# G888-mk2.net
KiCad netlist of a schematic drawn in EAGLE
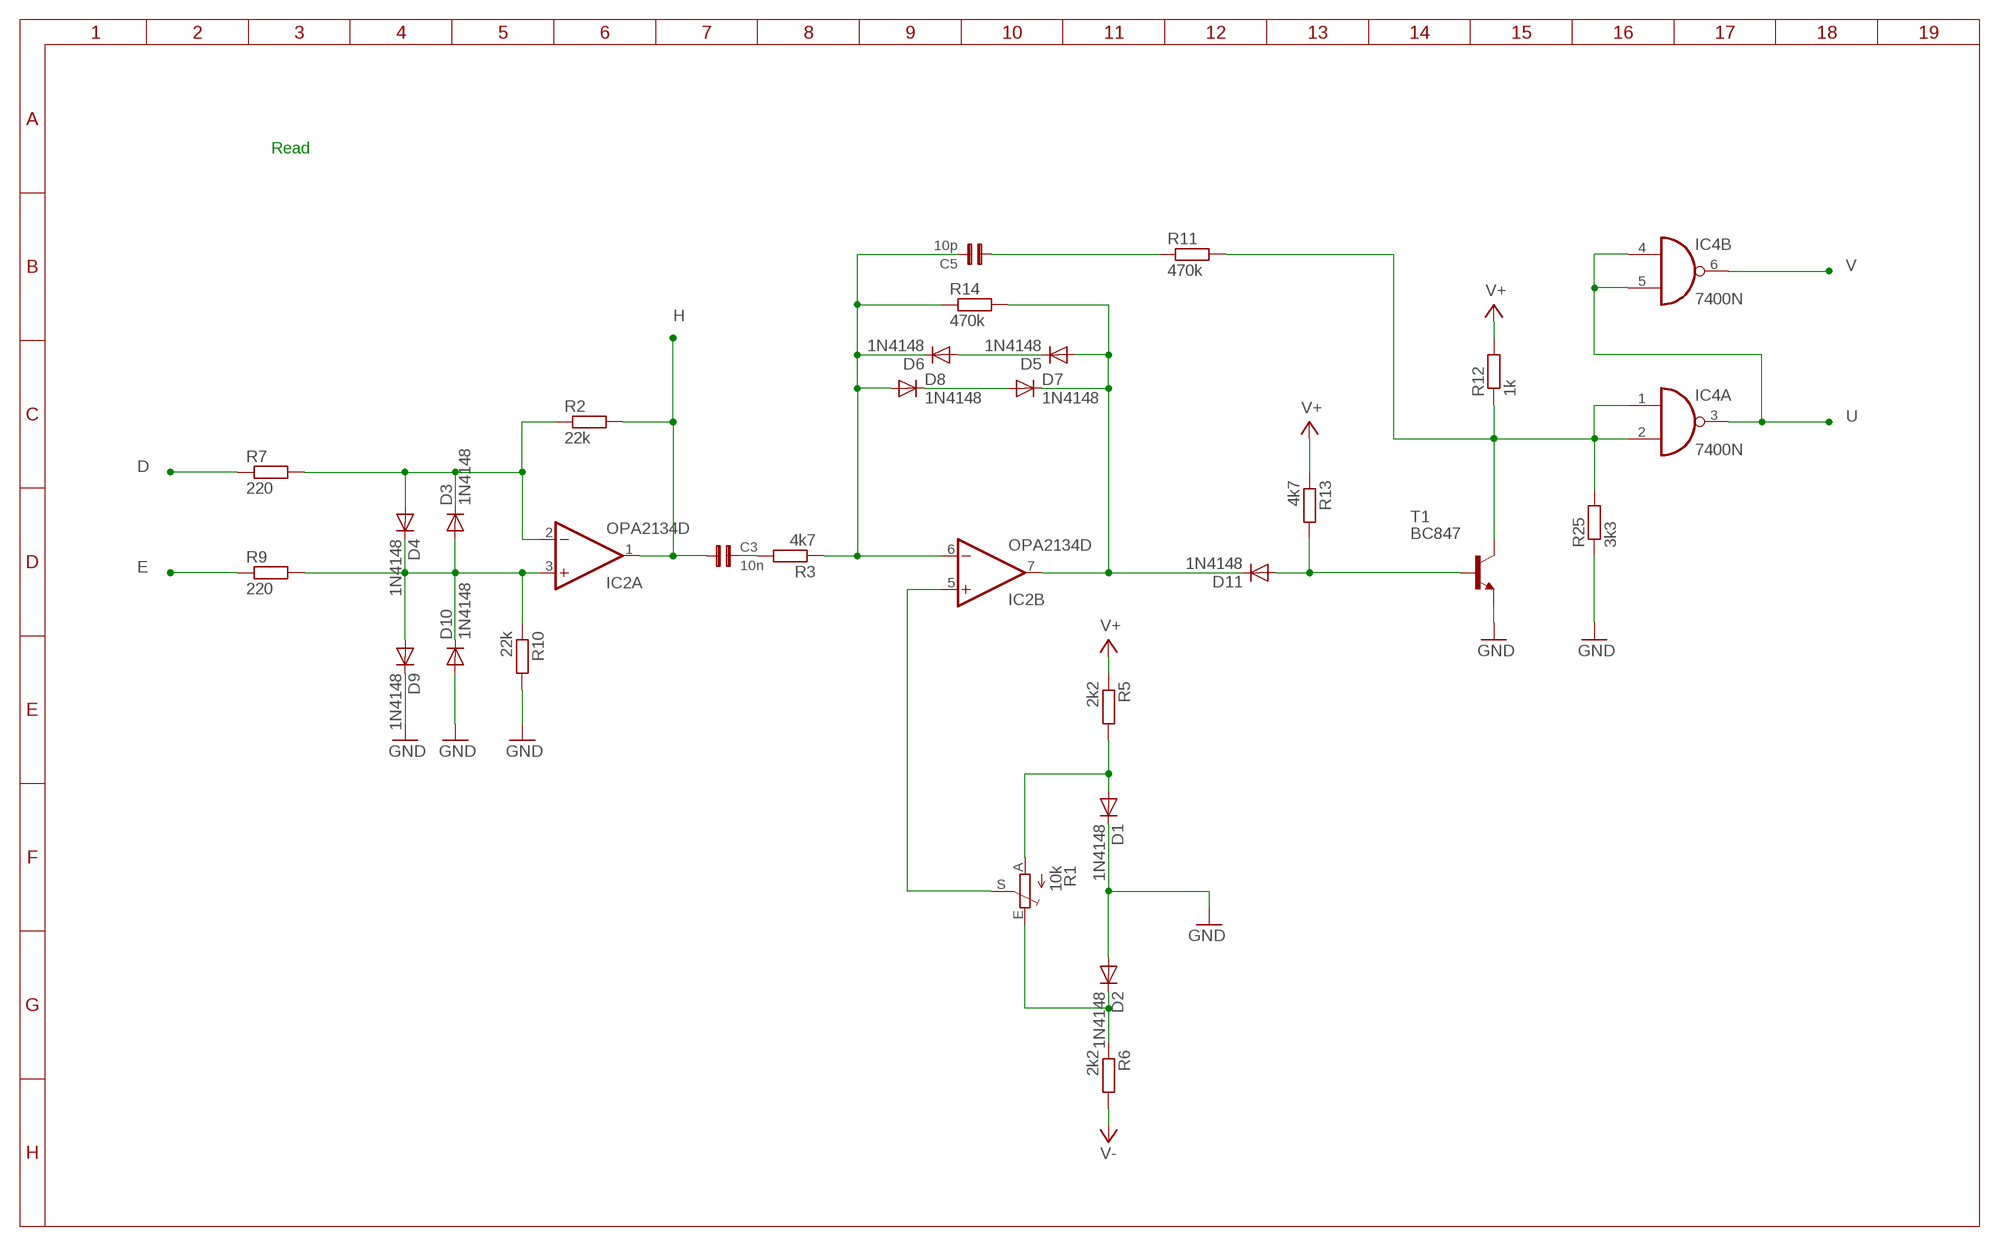
[diagram p0: schematic, sheet 1]
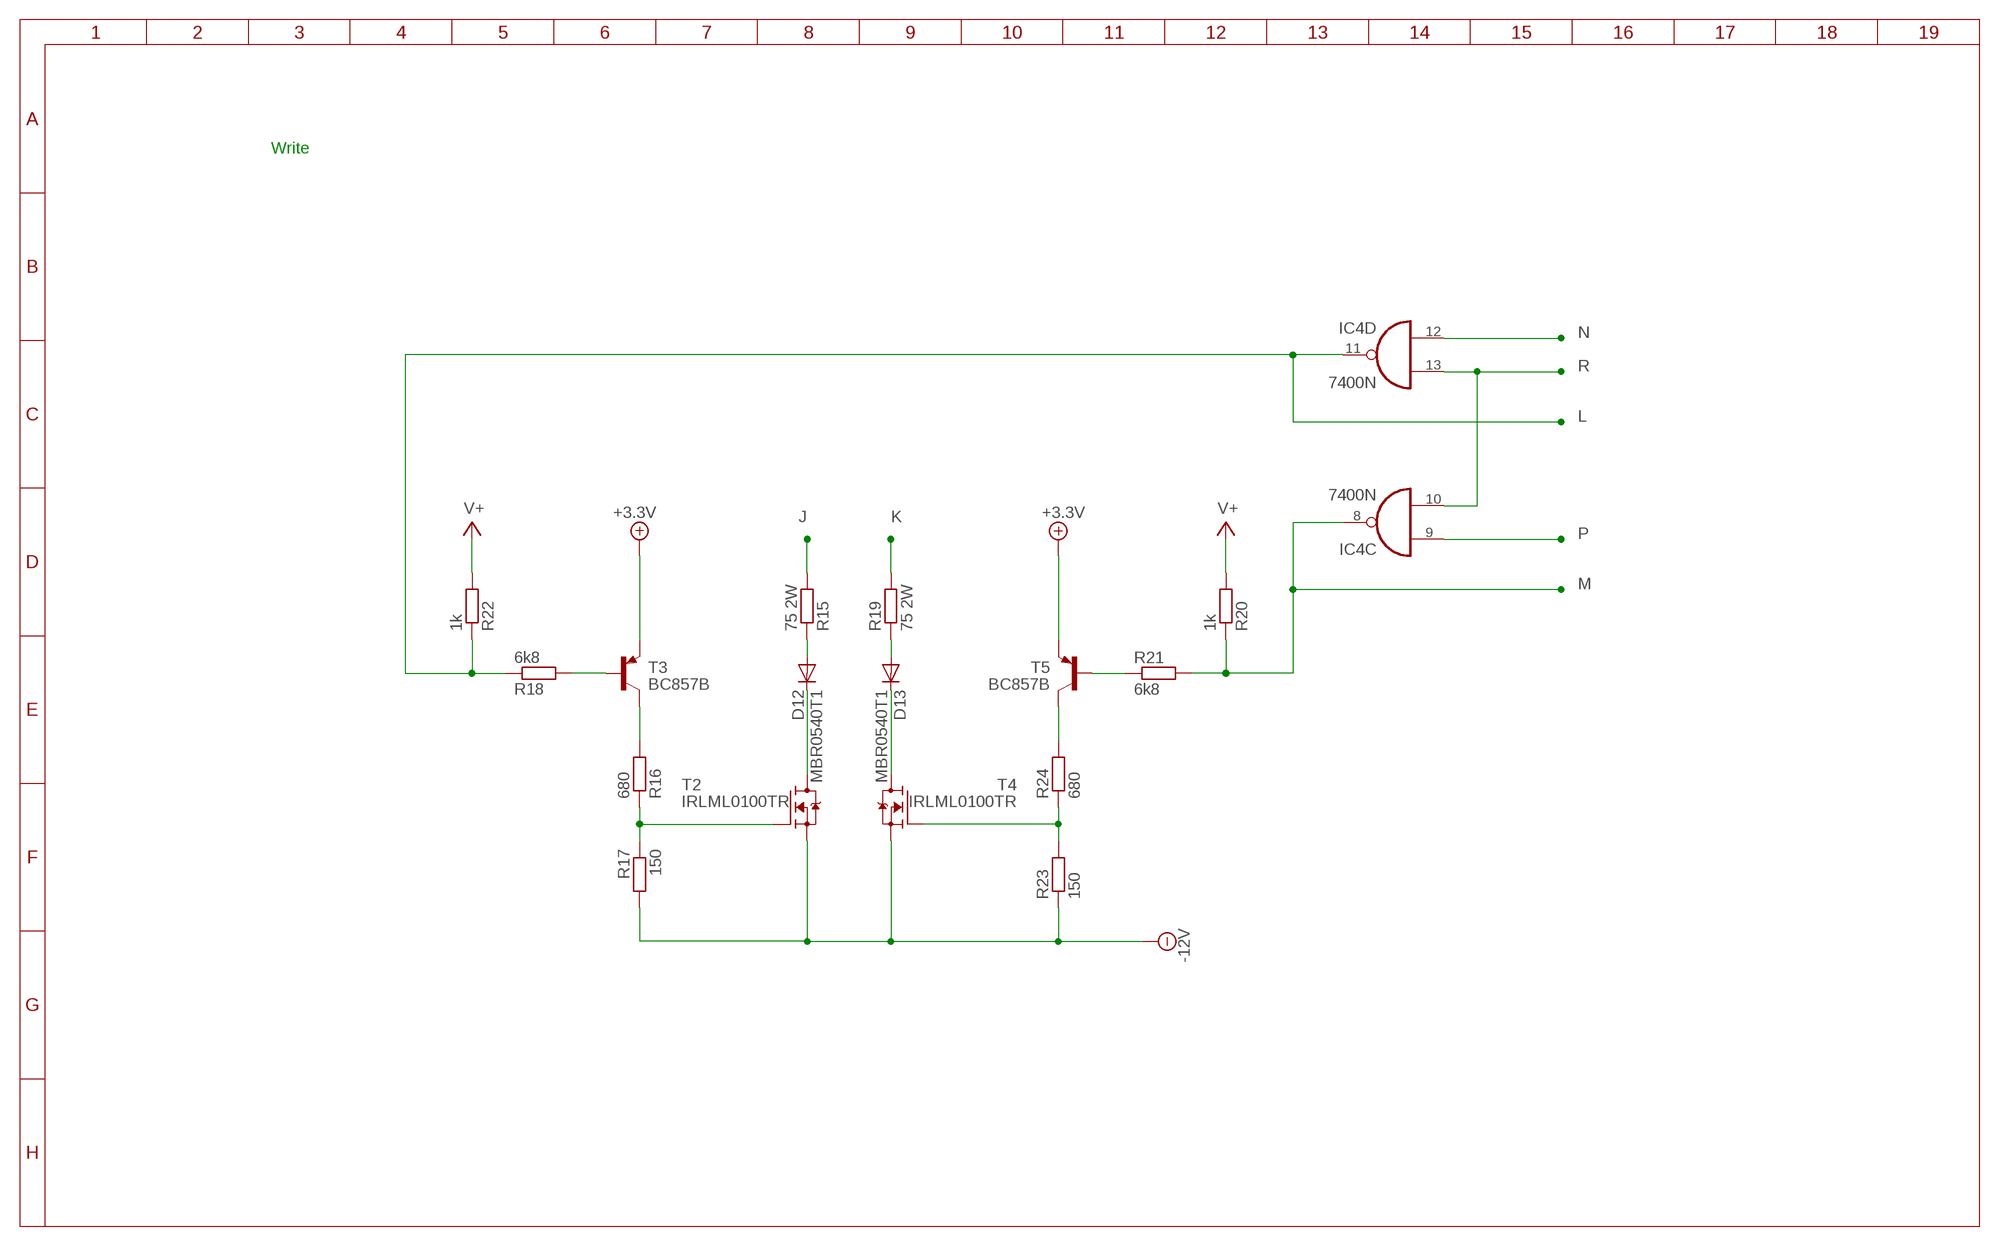
[diagram p1: schematic, sheet 2]
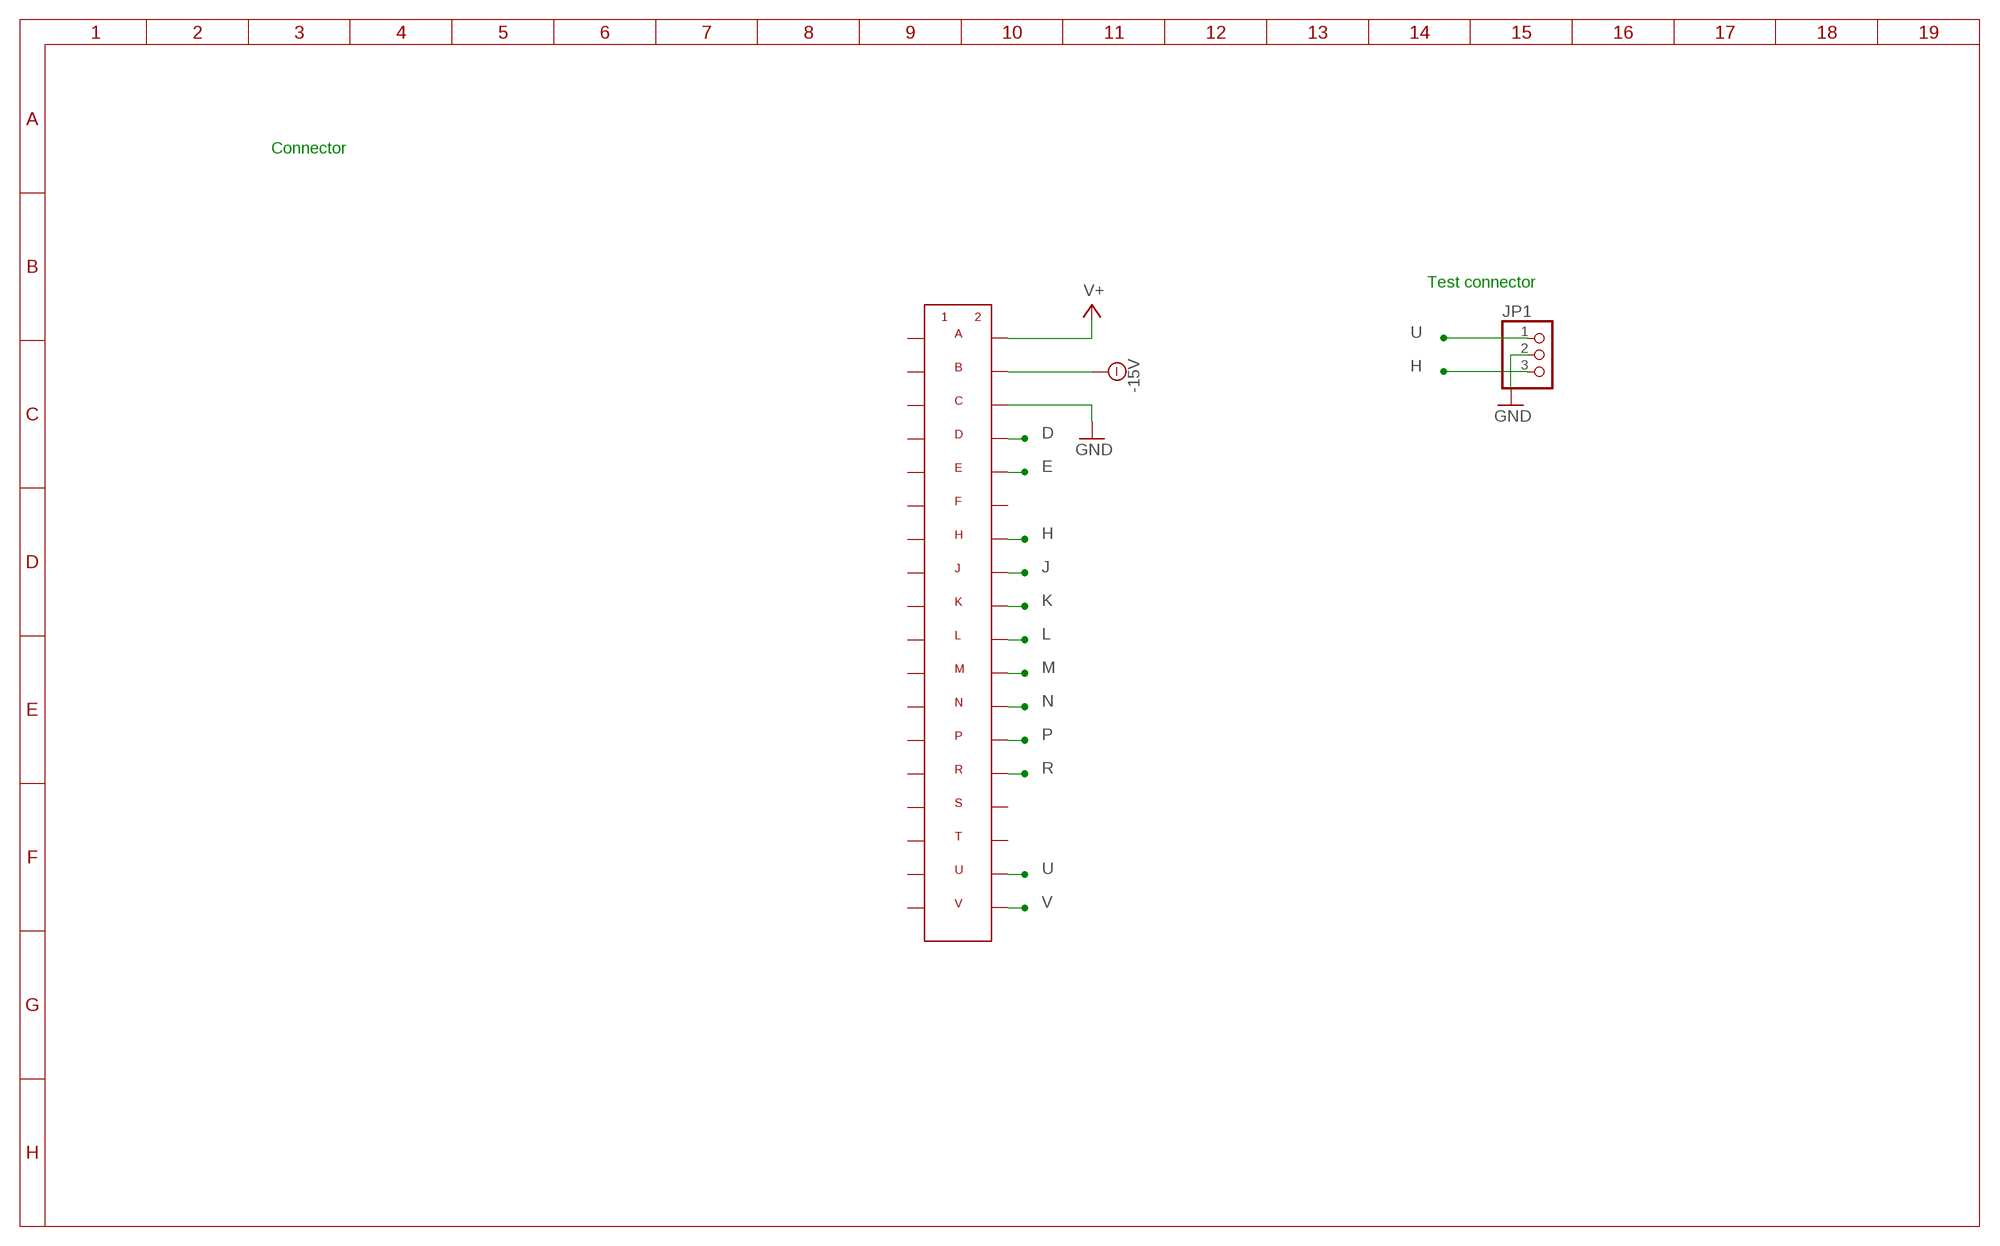
[diagram p2: schematic, sheet 3]
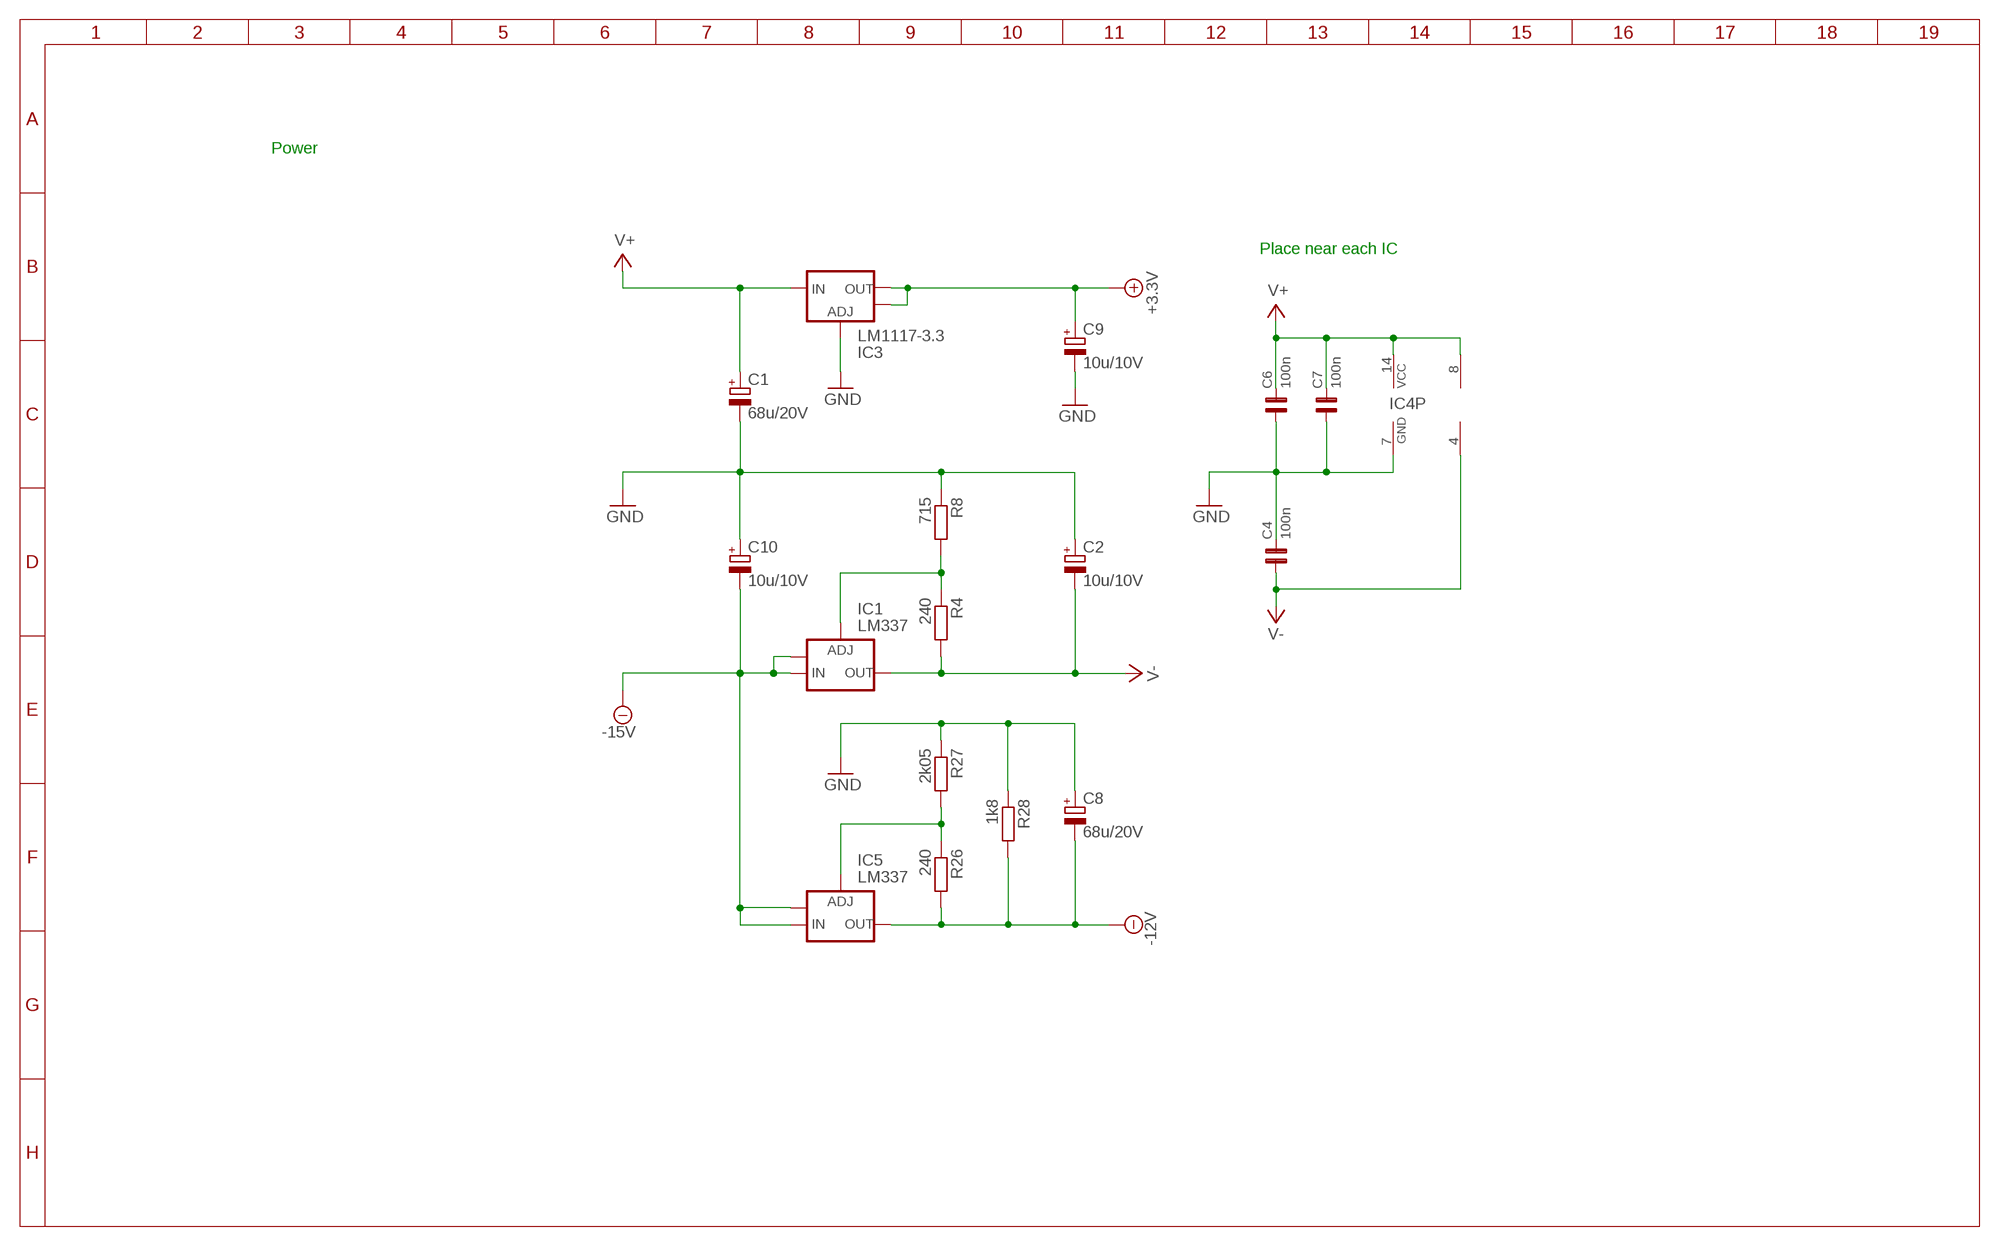
[diagram p3: schematic, sheet 4]

(export (version "E")
  (design (tool "Eeschema 10.0.6"))
  (components
    (comp (ref "C1")
      (value "68u/20V")
      (footprint "eagle-import:SMC_D")
      (libsource (lib "eagle-import") (part "CPOL-EUSMCD"))
    )
    (comp (ref "C2")
      (value "10u/10V")
      (footprint "eagle-import:SMC_C")
      (libsource (lib "eagle-import") (part "CPOL-EUSMCC"))
    )
    (comp (ref "C4")
      (value "100n")
      (footprint "eagle-import:0805")
      (libsource (lib "eagle-import") (part "C0805"))
    )
    (comp (ref "C6")
      (value "100n")
      (footprint "eagle-import:0805")
      (libsource (lib "eagle-import") (part "C0805"))
    )
    (comp (ref "C7")
      (value "100n")
      (footprint "eagle-import:0805")
      (libsource (lib "eagle-import") (part "C0805"))
    )
    (comp (ref "C8")
      (value "68u/20V")
      (footprint "eagle-import:SMC_D")
      (libsource (lib "eagle-import") (part "CPOL-EUSMCD"))
    )
    (comp (ref "C9")
      (value "10u/10V")
      (footprint "eagle-import:SMC_C")
      (libsource (lib "eagle-import") (part "CPOL-EUSMCC"))
    )
    (comp (ref "C10")
      (value "10u/10V")
      (footprint "eagle-import:SMC_C")
      (libsource (lib "eagle-import") (part "CPOL-EUSMCC"))
    )
    (comp (ref "IC1")
      (value "LM337")
      (footprint "eagle-import:SOT223")
      (libsource (lib "eagle-import") (part "LM337-SOT223"))
    )
    (comp (ref "IC2")
      (value "OPA2134D")
      (footprint "eagle-import:SOIC8")
      (libsource (lib "eagle-import") (part "OPA2134D"))
    )
    (comp (ref "IC3")
      (value "LM1117-3.3")
      (footprint "eagle-import:SOT223")
      (libsource (lib "eagle-import") (part "LM1117-3.3"))
    )
    (comp (ref "IC4")
      (value "7400N")
      (footprint "eagle-import:DIL14")
      (libsource (lib "eagle-import") (part "7400N"))
    )
    (comp (ref "IC5")
      (value "LM337")
      (footprint "eagle-import:SOT223")
      (libsource (lib "eagle-import") (part "LM337-SOT223"))
    )
    (comp (ref "R4")
      (value "240")
      (footprint "eagle-import:R0805")
      (libsource (lib "eagle-import") (part "R-EU_R0805"))
    )
    (comp (ref "R8")
      (value "715")
      (footprint "eagle-import:R0805")
      (libsource (lib "eagle-import") (part "R-EU_R0805"))
    )
    (comp (ref "R26")
      (value "240")
      (footprint "eagle-import:R0805")
      (libsource (lib "eagle-import") (part "R-EU_R0805"))
    )
    (comp (ref "R27")
      (value "2k05")
      (footprint "eagle-import:R0805")
      (libsource (lib "eagle-import") (part "R-EU_R0805"))
    )
    (comp (ref "R28")
      (value "1k8")
      (footprint "eagle-import:R0805")
      (libsource (lib "eagle-import") (part "R-EU_R0805"))
    )
    (comp (ref "CON1")
      (value "FLIPCHIP_1NORMAL")
      (footprint "eagle-import:FLIPCHIP-1")
      (libsource (lib "eagle-import") (part "FLIPCHIP_1NORMAL"))
    )
    (comp (ref "JP1")
      (value "PINHD-1X3/90")
      (footprint "eagle-import:1X03_90")
      (libsource (lib "eagle-import") (part "PINHD-1X3/90"))
    )
    (comp (ref "D12")
      (value "MBR0540T1")
      (footprint "eagle-import:SOD123")
      (libsource (lib "eagle-import") (part "MBR0540T1"))
    )
    (comp (ref "D13")
      (value "MBR0540T1")
      (footprint "eagle-import:SOD123")
      (libsource (lib "eagle-import") (part "MBR0540T1"))
    )
    (comp (ref "R15")
      (value "75 2W")
      (footprint "eagle-import:R2512")
      (libsource (lib "eagle-import") (part "R-EU_R2512"))
    )
    (comp (ref "R16")
      (value "680")
      (footprint "eagle-import:R0805")
      (libsource (lib "eagle-import") (part "R-EU_R0805"))
    )
    (comp (ref "R17")
      (value "150")
      (footprint "eagle-import:R0805")
      (libsource (lib "eagle-import") (part "R-EU_R0805"))
    )
    (comp (ref "R18")
      (value "6k8")
      (footprint "eagle-import:R0805")
      (libsource (lib "eagle-import") (part "R-EU_R0805"))
    )
    (comp (ref "R19")
      (value "75 2W")
      (footprint "eagle-import:R2512")
      (libsource (lib "eagle-import") (part "R-EU_R2512"))
    )
    (comp (ref "R20")
      (value "1k")
      (footprint "eagle-import:R0805")
      (libsource (lib "eagle-import") (part "R-EU_R0805"))
    )
    (comp (ref "R21")
      (value "6k8")
      (footprint "eagle-import:R0805")
      (libsource (lib "eagle-import") (part "R-EU_R0805"))
    )
    (comp (ref "R22")
      (value "1k")
      (footprint "eagle-import:R0805")
      (libsource (lib "eagle-import") (part "R-EU_R0805"))
    )
    (comp (ref "R23")
      (value "150")
      (footprint "eagle-import:R0805")
      (libsource (lib "eagle-import") (part "R-EU_R0805"))
    )
    (comp (ref "R24")
      (value "680")
      (footprint "eagle-import:R0805")
      (libsource (lib "eagle-import") (part "R-EU_R0805"))
    )
    (comp (ref "T2")
      (value "IRLML0100TR")
      (footprint "eagle-import:SOT23")
      (libsource (lib "eagle-import") (part "IRLML0100TR"))
    )
    (comp (ref "T3")
      (value "BC857B")
      (footprint "eagle-import:SOT23")
      (libsource (lib "eagle-import") (part "BC857B"))
    )
    (comp (ref "T4")
      (value "IRLML0100TR")
      (footprint "eagle-import:SOT23")
      (libsource (lib "eagle-import") (part "IRLML0100TR"))
    )
    (comp (ref "T5")
      (value "BC857B")
      (footprint "eagle-import:SOT23")
      (libsource (lib "eagle-import") (part "BC857B"))
    )
    (comp (ref "C3")
      (value "10n")
      (footprint "eagle-import:0805")
      (libsource (lib "eagle-import") (part "C0805"))
    )
    (comp (ref "C5")
      (value "10p")
      (footprint "eagle-import:0805")
      (libsource (lib "eagle-import") (part "C0805"))
    )
    (comp (ref "D1")
      (value "1N4148")
      (footprint "eagle-import:SOD123")
      (libsource (lib "eagle-import") (part "1N4148-Y"))
    )
    (comp (ref "D2")
      (value "1N4148")
      (footprint "eagle-import:SOD123")
      (libsource (lib "eagle-import") (part "1N4148-Y"))
    )
    (comp (ref "D3")
      (value "1N4148")
      (footprint "eagle-import:SOD123")
      (libsource (lib "eagle-import") (part "1N4148-Y"))
    )
    (comp (ref "D4")
      (value "1N4148")
      (footprint "eagle-import:SOD123")
      (libsource (lib "eagle-import") (part "1N4148-Y"))
    )
    (comp (ref "D5")
      (value "1N4148")
      (footprint "eagle-import:SOD123")
      (libsource (lib "eagle-import") (part "1N4148-Y"))
    )
    (comp (ref "D6")
      (value "1N4148")
      (footprint "eagle-import:SOD123")
      (libsource (lib "eagle-import") (part "1N4148-Y"))
    )
    (comp (ref "D7")
      (value "1N4148")
      (footprint "eagle-import:SOD123")
      (libsource (lib "eagle-import") (part "1N4148-Y"))
    )
    (comp (ref "D8")
      (value "1N4148")
      (footprint "eagle-import:SOD123")
      (libsource (lib "eagle-import") (part "1N4148-Y"))
    )
    (comp (ref "D9")
      (value "1N4148")
      (footprint "eagle-import:SOD123")
      (libsource (lib "eagle-import") (part "1N4148-Y"))
    )
    (comp (ref "D10")
      (value "1N4148")
      (footprint "eagle-import:SOD123")
      (libsource (lib "eagle-import") (part "1N4148-Y"))
    )
    (comp (ref "D11")
      (value "1N4148")
      (footprint "eagle-import:SOD123")
      (libsource (lib "eagle-import") (part "1N4148-Y"))
    )
    (comp (ref "R1")
      (value "10k")
      (footprint "eagle-import:SP19L")
      (libsource (lib "eagle-import") (part "TRIM_EU-SP19L"))
    )
    (comp (ref "R2")
      (value "22k")
      (footprint "eagle-import:R0805")
      (libsource (lib "eagle-import") (part "R-EU_R0805"))
    )
    (comp (ref "R3")
      (value "4k7")
      (footprint "eagle-import:R0805")
      (libsource (lib "eagle-import") (part "R-EU_R0805"))
    )
    (comp (ref "R5")
      (value "2k2")
      (footprint "eagle-import:R0805")
      (libsource (lib "eagle-import") (part "R-EU_R0805"))
    )
    (comp (ref "R6")
      (value "2k2")
      (footprint "eagle-import:R0805")
      (libsource (lib "eagle-import") (part "R-EU_R0805"))
    )
    (comp (ref "R7")
      (value "220")
      (footprint "eagle-import:R0805")
      (libsource (lib "eagle-import") (part "R-EU_R0805"))
    )
    (comp (ref "R9")
      (value "220")
      (footprint "eagle-import:R0805")
      (libsource (lib "eagle-import") (part "R-EU_R0805"))
    )
    (comp (ref "R10")
      (value "22k")
      (footprint "eagle-import:R0805")
      (libsource (lib "eagle-import") (part "R-EU_R0805"))
    )
    (comp (ref "R11")
      (value "470k")
      (footprint "eagle-import:R0805")
      (libsource (lib "eagle-import") (part "R-EU_R0805"))
    )
    (comp (ref "R12")
      (value "1k")
      (footprint "eagle-import:R0805")
      (libsource (lib "eagle-import") (part "R-EU_R0805"))
    )
    (comp (ref "R13")
      (value "4k7")
      (footprint "eagle-import:R0805")
      (libsource (lib "eagle-import") (part "R-EU_R0805"))
    )
    (comp (ref "R14")
      (value "470k")
      (footprint "eagle-import:R0805")
      (libsource (lib "eagle-import") (part "R-EU_R0805"))
    )
    (comp (ref "R25")
      (value "3k3")
      (footprint "eagle-import:R0805")
      (libsource (lib "eagle-import") (part "R-EU_R0805"))
    )
    (comp (ref "T1")
      (value "BC847")
      (footprint "eagle-import:SOT23")
      (libsource (lib "eagle-import") (part "BC847"))
    )
  )
  (nets
    (net (code "1") (name "+3.3V") (class "Default")
      (node (ref "C9") (pin "+") (pinfunction "+_+") (pintype "passive"))
      (node (ref "IC3") (pin "2") (pinfunction "OUT_2") (pintype "passive"))
      (node (ref "IC3") (pin "4") (pinfunction "OUT_TAB_4") (pintype "passive"))
      (node (ref "T3") (pin "2") (pinfunction "E_2") (pintype "passive"))
      (node (ref "T5") (pin "2") (pinfunction "E_2") (pintype "passive"))
    )
    (net (code "2") (name "-12V") (class "Default")
      (node (ref "C8") (pin "-") (pinfunction "-_-") (pintype "passive"))
      (node (ref "IC5") (pin "3") (pinfunction "OUT_3") (pintype "passive"))
      (node (ref "R17") (pin "2") (pinfunction "2_2") (pintype "passive"))
      (node (ref "R23") (pin "1") (pinfunction "1_1") (pintype "passive"))
      (node (ref "R26") (pin "2") (pinfunction "2_2") (pintype "passive"))
      (node (ref "R28") (pin "2") (pinfunction "2_2") (pintype "passive"))
      (node (ref "T2") (pin "2") (pinfunction "S_2") (pintype "passive"))
      (node (ref "T4") (pin "2") (pinfunction "S_2") (pintype "passive"))
    )
    (net (code "3") (name "-15V") (class "Default")
      (node (ref "C10") (pin "-") (pinfunction "-_-") (pintype "passive"))
      (node (ref "CON1") (pin "B2") (pinfunction "B2_B2") (pintype "bidirectional"))
      (node (ref "IC1") (pin "2") (pinfunction "IN_2") (pintype "input"))
      (node (ref "IC1") (pin "4") (pinfunction "IN_TAB_4") (pintype "input"))
      (node (ref "IC5") (pin "2") (pinfunction "IN_2") (pintype "input"))
      (node (ref "IC5") (pin "4") (pinfunction "IN_TAB_4") (pintype "input"))
    )
    (net (code "4") (name "D") (class "Default")
      (node (ref "CON1") (pin "D2") (pinfunction "D2_D2") (pintype "bidirectional"))
      (node (ref "R7") (pin "1") (pinfunction "1_1") (pintype "passive"))
    )
    (net (code "5") (name "E") (class "Default")
      (node (ref "CON1") (pin "E2") (pinfunction "E2_E2") (pintype "bidirectional"))
      (node (ref "R9") (pin "1") (pinfunction "1_1") (pintype "passive"))
    )
    (net (code "6") (name "GND") (class "Default")
      (node (ref "C1") (pin "-") (pinfunction "-_-") (pintype "passive"))
      (node (ref "C10") (pin "+") (pinfunction "+_+") (pintype "passive"))
      (node (ref "C2") (pin "+") (pinfunction "+_+") (pintype "passive"))
      (node (ref "C4") (pin "2") (pinfunction "2_2") (pintype "passive"))
      (node (ref "C6") (pin "1") (pinfunction "1_1") (pintype "passive"))
      (node (ref "C7") (pin "1") (pinfunction "1_1") (pintype "passive"))
      (node (ref "C8") (pin "+") (pinfunction "+_+") (pintype "passive"))
      (node (ref "C9") (pin "-") (pinfunction "-_-") (pintype "passive"))
      (node (ref "CON1") (pin "C2") (pinfunction "C2_C2") (pintype "bidirectional"))
      (node (ref "D1") (pin "C") (pinfunction "C_C") (pintype "passive"))
      (node (ref "D10") (pin "A") (pinfunction "A_A") (pintype "passive"))
      (node (ref "D2") (pin "A") (pinfunction "A_A") (pintype "passive"))
      (node (ref "D9") (pin "C") (pinfunction "C_C") (pintype "passive"))
      (node (ref "IC3") (pin "1") (pinfunction "GND_1") (pintype "input"))
      (node (ref "IC4") (pin "7") (pinfunction "GND_7") (pintype "power_in"))
      (node (ref "JP1") (pin "2") (pinfunction "2_2") (pintype "passive"))
      (node (ref "R10") (pin "2") (pinfunction "2_2") (pintype "passive"))
      (node (ref "R25") (pin "1") (pinfunction "1_1") (pintype "passive"))
      (node (ref "R27") (pin "1") (pinfunction "1_1") (pintype "passive"))
      (node (ref "R28") (pin "1") (pinfunction "1_1") (pintype "passive"))
      (node (ref "R8") (pin "1") (pinfunction "1_1") (pintype "passive"))
      (node (ref "T1") (pin "2") (pinfunction "E_2") (pintype "passive"))
    )
    (net (code "7") (name "H") (class "Default")
      (node (ref "C3") (pin "1") (pinfunction "1_1") (pintype "passive"))
      (node (ref "CON1") (pin "H2") (pinfunction "G2_H2") (pintype "bidirectional"))
      (node (ref "IC2") (pin "1") (pinfunction "OUT_1") (pintype "output"))
      (node (ref "JP1") (pin "3") (pinfunction "3_3") (pintype "passive"))
      (node (ref "R2") (pin "2") (pinfunction "2_2") (pintype "passive"))
    )
    (net (code "8") (name "J") (class "Default")
      (node (ref "CON1") (pin "J2") (pinfunction "J2_J2") (pintype "bidirectional"))
      (node (ref "R15") (pin "2") (pinfunction "2_2") (pintype "passive"))
    )
    (net (code "9") (name "K") (class "Default")
      (node (ref "CON1") (pin "K2") (pinfunction "K2_K2") (pintype "bidirectional"))
      (node (ref "R19") (pin "2") (pinfunction "2_2") (pintype "passive"))
    )
    (net (code "10") (name "L") (class "Default")
      (node (ref "CON1") (pin "L2") (pinfunction "L2_L2") (pintype "bidirectional"))
      (node (ref "IC4") (pin "11") (pinfunction "O_11") (pintype "output"))
      (node (ref "R18") (pin "1") (pinfunction "1_1") (pintype "passive"))
      (node (ref "R22") (pin "1") (pinfunction "1_1") (pintype "passive"))
    )
    (net (code "11") (name "M") (class "Default")
      (node (ref "CON1") (pin "M2") (pinfunction "M2_M2") (pintype "bidirectional"))
      (node (ref "IC4") (pin "8") (pinfunction "O_8") (pintype "output"))
      (node (ref "R20") (pin "1") (pinfunction "1_1") (pintype "passive"))
      (node (ref "R21") (pin "2") (pinfunction "2_2") (pintype "passive"))
    )
    (net (code "12") (name "N") (class "Default")
      (node (ref "CON1") (pin "N2") (pinfunction "N2_N2") (pintype "bidirectional"))
      (node (ref "IC4") (pin "12") (pinfunction "I0_12") (pintype "input"))
    )
    (net (code "13") (name "Net-(C3-Pad2)") (class "Default")
      (node (ref "C3") (pin "2") (pinfunction "2_2") (pintype "passive"))
      (node (ref "R3") (pin "2") (pinfunction "2_2") (pintype "passive"))
    )
    (net (code "14") (name "Net-(C5-Pad1)") (class "Default")
      (node (ref "C5") (pin "1") (pinfunction "1_1") (pintype "passive"))
      (node (ref "R11") (pin "1") (pinfunction "1_1") (pintype "passive"))
    )
    (net (code "15") (name "Net-(D1-PadA)") (class "Default")
      (node (ref "D1") (pin "A") (pinfunction "A_A") (pintype "passive"))
      (node (ref "R1") (pin "A") (pinfunction "A_A") (pintype "passive"))
      (node (ref "R5") (pin "2") (pinfunction "2_2") (pintype "passive"))
    )
    (net (code "16") (name "Net-(D2-PadC)") (class "Default")
      (node (ref "D2") (pin "C") (pinfunction "C_C") (pintype "passive"))
      (node (ref "R1") (pin "E") (pinfunction "E_E") (pintype "passive"))
      (node (ref "R6") (pin "1") (pinfunction "1_1") (pintype "passive"))
    )
    (net (code "17") (name "Net-(D5-PadC)") (class "Default")
      (node (ref "D5") (pin "C") (pinfunction "C_C") (pintype "passive"))
      (node (ref "D6") (pin "A") (pinfunction "A_A") (pintype "passive"))
    )
    (net (code "18") (name "Net-(D7-PadA)") (class "Default")
      (node (ref "D7") (pin "A") (pinfunction "A_A") (pintype "passive"))
      (node (ref "D8") (pin "C") (pinfunction "C_C") (pintype "passive"))
    )
    (net (code "19") (name "Net-(D12-PadA)") (class "Default")
      (node (ref "D12") (pin "A") (pinfunction "A_A") (pintype "passive"))
      (node (ref "R15") (pin "1") (pinfunction "1_1") (pintype "passive"))
    )
    (net (code "20") (name "Net-(D13-PadA)") (class "Default")
      (node (ref "D13") (pin "A") (pinfunction "A_A") (pintype "passive"))
      (node (ref "R19") (pin "1") (pinfunction "1_1") (pintype "passive"))
    )
    (net (code "21") (name "Net-(IC1-ADJ)") (class "Default")
      (node (ref "IC1") (pin "1") (pinfunction "ADJ_1") (pintype "input"))
      (node (ref "R4") (pin "1") (pinfunction "1_1") (pintype "passive"))
      (node (ref "R8") (pin "2") (pinfunction "2_2") (pintype "passive"))
    )
    (net (code "22") (name "Net-(IC2A-+IN)") (class "Default")
      (node (ref "D10") (pin "C") (pinfunction "C_C") (pintype "passive"))
      (node (ref "D3") (pin "A") (pinfunction "A_A") (pintype "passive"))
      (node (ref "D4") (pin "C") (pinfunction "C_C") (pintype "passive"))
      (node (ref "D9") (pin "A") (pinfunction "A_A") (pintype "passive"))
      (node (ref "IC2") (pin "3") (pinfunction "+IN_3") (pintype "input"))
      (node (ref "R10") (pin "1") (pinfunction "1_1") (pintype "passive"))
      (node (ref "R9") (pin "2") (pinfunction "2_2") (pintype "passive"))
    )
    (net (code "23") (name "Net-(IC2A--IN)") (class "Default")
      (node (ref "D3") (pin "C") (pinfunction "C_C") (pintype "passive"))
      (node (ref "D4") (pin "A") (pinfunction "A_A") (pintype "passive"))
      (node (ref "IC2") (pin "2") (pinfunction "-IN_2") (pintype "input"))
      (node (ref "R2") (pin "1") (pinfunction "1_1") (pintype "passive"))
      (node (ref "R7") (pin "2") (pinfunction "2_2") (pintype "passive"))
    )
    (net (code "24") (name "Net-(IC2B-+IN)") (class "Default")
      (node (ref "IC2") (pin "5") (pinfunction "+IN_5") (pintype "input"))
      (node (ref "R1") (pin "S") (pinfunction "S_S") (pintype "passive"))
    )
    (net (code "25") (name "Net-(IC2B--IN)") (class "Default")
      (node (ref "C5") (pin "2") (pinfunction "2_2") (pintype "passive"))
      (node (ref "D6") (pin "C") (pinfunction "C_C") (pintype "passive"))
      (node (ref "D8") (pin "A") (pinfunction "A_A") (pintype "passive"))
      (node (ref "IC2") (pin "6") (pinfunction "-IN_6") (pintype "input"))
      (node (ref "R14") (pin "1") (pinfunction "1_1") (pintype "passive"))
      (node (ref "R3") (pin "1") (pinfunction "1_1") (pintype "passive"))
    )
    (net (code "26") (name "Net-(IC2B-OUT)") (class "Default")
      (node (ref "D11") (pin "C") (pinfunction "C_C") (pintype "passive"))
      (node (ref "D5") (pin "A") (pinfunction "A_A") (pintype "passive"))
      (node (ref "D7") (pin "C") (pinfunction "C_C") (pintype "passive"))
      (node (ref "IC2") (pin "7") (pinfunction "OUT_7") (pintype "output"))
      (node (ref "R14") (pin "2") (pinfunction "2_2") (pintype "passive"))
    )
    (net (code "27") (name "Net-(IC4A-I0)") (class "Default")
      (node (ref "IC4") (pin "1") (pinfunction "I0_1") (pintype "input"))
      (node (ref "IC4") (pin "2") (pinfunction "I1_2") (pintype "input"))
      (node (ref "R11") (pin "2") (pinfunction "2_2") (pintype "passive"))
      (node (ref "R12") (pin "1") (pinfunction "1_1") (pintype "passive"))
      (node (ref "R25") (pin "2") (pinfunction "2_2") (pintype "passive"))
      (node (ref "T1") (pin "3") (pinfunction "C_3") (pintype "passive"))
    )
    (net (code "28") (name "Net-(IC5-ADJ)") (class "Default")
      (node (ref "IC5") (pin "1") (pinfunction "ADJ_1") (pintype "input"))
      (node (ref "R26") (pin "1") (pinfunction "1_1") (pintype "passive"))
      (node (ref "R27") (pin "2") (pinfunction "2_2") (pintype "passive"))
    )
    (net (code "29") (name "Net-(T1-B)") (class "Default")
      (node (ref "D11") (pin "A") (pinfunction "A_A") (pintype "passive"))
      (node (ref "R13") (pin "2") (pinfunction "2_2") (pintype "passive"))
      (node (ref "T1") (pin "1") (pinfunction "B_1") (pintype "passive"))
    )
    (net (code "30") (name "Net-(T2-D)") (class "Default")
      (node (ref "D12") (pin "C") (pinfunction "C_C") (pintype "passive"))
      (node (ref "T2") (pin "3") (pinfunction "D_3") (pintype "passive"))
    )
    (net (code "31") (name "Net-(T2-G)") (class "Default")
      (node (ref "R16") (pin "1") (pinfunction "1_1") (pintype "passive"))
      (node (ref "R17") (pin "1") (pinfunction "1_1") (pintype "passive"))
      (node (ref "T2") (pin "1") (pinfunction "G_1") (pintype "passive"))
    )
    (net (code "32") (name "Net-(T3-B)") (class "Default")
      (node (ref "R18") (pin "2") (pinfunction "2_2") (pintype "passive"))
      (node (ref "T3") (pin "1") (pinfunction "B_1") (pintype "passive"))
    )
    (net (code "33") (name "Net-(T3-C)") (class "Default")
      (node (ref "R16") (pin "2") (pinfunction "2_2") (pintype "passive"))
      (node (ref "T3") (pin "3") (pinfunction "C_3") (pintype "passive"))
    )
    (net (code "34") (name "Net-(T4-D)") (class "Default")
      (node (ref "D13") (pin "C") (pinfunction "C_C") (pintype "passive"))
      (node (ref "T4") (pin "3") (pinfunction "D_3") (pintype "passive"))
    )
    (net (code "35") (name "Net-(T4-G)") (class "Default")
      (node (ref "R23") (pin "2") (pinfunction "2_2") (pintype "passive"))
      (node (ref "R24") (pin "1") (pinfunction "1_1") (pintype "passive"))
      (node (ref "T4") (pin "1") (pinfunction "G_1") (pintype "passive"))
    )
    (net (code "36") (name "Net-(T5-B)") (class "Default")
      (node (ref "R21") (pin "1") (pinfunction "1_1") (pintype "passive"))
      (node (ref "T5") (pin "1") (pinfunction "B_1") (pintype "passive"))
    )
    (net (code "37") (name "Net-(T5-C)") (class "Default")
      (node (ref "R24") (pin "2") (pinfunction "2_2") (pintype "passive"))
      (node (ref "T5") (pin "3") (pinfunction "C_3") (pintype "passive"))
    )
    (net (code "38") (name "P") (class "Default")
      (node (ref "CON1") (pin "P2") (pinfunction "P2_P2") (pintype "bidirectional"))
      (node (ref "IC4") (pin "9") (pinfunction "I0_9") (pintype "input"))
    )
    (net (code "39") (name "R") (class "Default")
      (node (ref "CON1") (pin "R2") (pinfunction "R2_R2") (pintype "bidirectional"))
      (node (ref "IC4") (pin "10") (pinfunction "I1_10") (pintype "input"))
      (node (ref "IC4") (pin "13") (pinfunction "I1_13") (pintype "input"))
    )
    (net (code "40") (name "U") (class "Default")
      (node (ref "CON1") (pin "U2") (pinfunction "U2_U2") (pintype "bidirectional"))
      (node (ref "IC4") (pin "3") (pinfunction "O_3") (pintype "output"))
      (node (ref "IC4") (pin "4") (pinfunction "I0_4") (pintype "input"))
      (node (ref "IC4") (pin "5") (pinfunction "I1_5") (pintype "input"))
      (node (ref "JP1") (pin "1") (pinfunction "1_1") (pintype "passive"))
    )
    (net (code "41") (name "V") (class "Default")
      (node (ref "CON1") (pin "V2") (pinfunction "V2_V2") (pintype "bidirectional"))
      (node (ref "IC4") (pin "6") (pinfunction "O_6") (pintype "output"))
    )
    (net (code "42") (name "V+") (class "Default")
      (node (ref "C1") (pin "+") (pinfunction "+_+") (pintype "passive"))
      (node (ref "C6") (pin "2") (pinfunction "2_2") (pintype "passive"))
      (node (ref "C7") (pin "2") (pinfunction "2_2") (pintype "passive"))
      (node (ref "CON1") (pin "A2") (pinfunction "A2_A2") (pintype "bidirectional"))
      (node (ref "IC2") (pin "8") (pinfunction "V+_8") (pintype "power_in"))
      (node (ref "IC3") (pin "3") (pinfunction "IN_3") (pintype "input"))
      (node (ref "IC4") (pin "14") (pinfunction "VCC_14") (pintype "power_in"))
      (node (ref "R12") (pin "2") (pinfunction "2_2") (pintype "passive"))
      (node (ref "R13") (pin "1") (pinfunction "1_1") (pintype "passive"))
      (node (ref "R20") (pin "2") (pinfunction "2_2") (pintype "passive"))
      (node (ref "R22") (pin "2") (pinfunction "2_2") (pintype "passive"))
      (node (ref "R5") (pin "1") (pinfunction "1_1") (pintype "passive"))
    )
    (net (code "43") (name "V-") (class "Default")
      (node (ref "C2") (pin "-") (pinfunction "-_-") (pintype "passive"))
      (node (ref "C4") (pin "1") (pinfunction "1_1") (pintype "passive"))
      (node (ref "IC1") (pin "3") (pinfunction "OUT_3") (pintype "passive"))
      (node (ref "IC2") (pin "4") (pinfunction "V-_4") (pintype "power_in"))
      (node (ref "R4") (pin "2") (pinfunction "2_2") (pintype "passive"))
      (node (ref "R6") (pin "2") (pinfunction "2_2") (pintype "passive"))
    )
    (net (code "44") (name "unconnected-(CON1-PadA1)") (class "Default")
      (node (ref "CON1") (pin "A1") (pinfunction "A1_A1") (pintype "bidirectional"))
    )
    (net (code "45") (name "unconnected-(CON1-PadB1)") (class "Default")
      (node (ref "CON1") (pin "B1") (pinfunction "B1_B1") (pintype "bidirectional"))
    )
    (net (code "46") (name "unconnected-(CON1-PadC1)") (class "Default")
      (node (ref "CON1") (pin "C1") (pinfunction "C1_C1") (pintype "bidirectional"))
    )
    (net (code "47") (name "unconnected-(CON1-PadD1)") (class "Default")
      (node (ref "CON1") (pin "D1") (pinfunction "D1_D1") (pintype "bidirectional"))
    )
    (net (code "48") (name "unconnected-(CON1-PadE1)") (class "Default")
      (node (ref "CON1") (pin "E1") (pinfunction "E1_E1") (pintype "bidirectional"))
    )
    (net (code "49") (name "unconnected-(CON1-PadF1)") (class "Default")
      (node (ref "CON1") (pin "F1") (pinfunction "F1_F1") (pintype "bidirectional"))
    )
    (net (code "50") (name "unconnected-(CON1-PadF2)") (class "Default")
      (node (ref "CON1") (pin "F2") (pinfunction "F2_F2") (pintype "bidirectional"))
    )
    (net (code "51") (name "unconnected-(CON1-PadH1)") (class "Default")
      (node (ref "CON1") (pin "H1") (pinfunction "H1_H1") (pintype "bidirectional"))
    )
    (net (code "52") (name "unconnected-(CON1-PadJ1)") (class "Default")
      (node (ref "CON1") (pin "J1") (pinfunction "J1_J1") (pintype "bidirectional"))
    )
    (net (code "53") (name "unconnected-(CON1-PadK1)") (class "Default")
      (node (ref "CON1") (pin "K1") (pinfunction "K1_K1") (pintype "bidirectional"))
    )
    (net (code "54") (name "unconnected-(CON1-PadL1)") (class "Default")
      (node (ref "CON1") (pin "L1") (pinfunction "L1_L1") (pintype "bidirectional"))
    )
    (net (code "55") (name "unconnected-(CON1-PadM1)") (class "Default")
      (node (ref "CON1") (pin "M1") (pinfunction "M1_M1") (pintype "bidirectional"))
    )
    (net (code "56") (name "unconnected-(CON1-PadN1)") (class "Default")
      (node (ref "CON1") (pin "N1") (pinfunction "N1_N1") (pintype "bidirectional"))
    )
    (net (code "57") (name "unconnected-(CON1-PadP1)") (class "Default")
      (node (ref "CON1") (pin "P1") (pinfunction "P1_P1") (pintype "bidirectional"))
    )
    (net (code "58") (name "unconnected-(CON1-PadR1)") (class "Default")
      (node (ref "CON1") (pin "R1") (pinfunction "R1_R1") (pintype "bidirectional"))
    )
    (net (code "59") (name "unconnected-(CON1-PadS1)") (class "Default")
      (node (ref "CON1") (pin "S1") (pinfunction "S1_S1") (pintype "bidirectional"))
    )
    (net (code "60") (name "unconnected-(CON1-PadS2)") (class "Default")
      (node (ref "CON1") (pin "S2") (pinfunction "S2_S2") (pintype "bidirectional"))
    )
    (net (code "61") (name "unconnected-(CON1-PadT1)") (class "Default")
      (node (ref "CON1") (pin "T1") (pinfunction "T1_T1") (pintype "bidirectional"))
    )
    (net (code "62") (name "unconnected-(CON1-PadT2)") (class "Default")
      (node (ref "CON1") (pin "T2") (pinfunction "T2_T2") (pintype "bidirectional"))
    )
    (net (code "63") (name "unconnected-(CON1-PadU1)") (class "Default")
      (node (ref "CON1") (pin "U1") (pinfunction "U1_U1") (pintype "bidirectional"))
    )
    (net (code "64") (name "unconnected-(CON1-PadV1)") (class "Default")
      (node (ref "CON1") (pin "V1") (pinfunction "V1_V1") (pintype "bidirectional"))
    )
  )
)
